# digital_supply.net
KiCad netlist of a schematic drawn in EAGLE
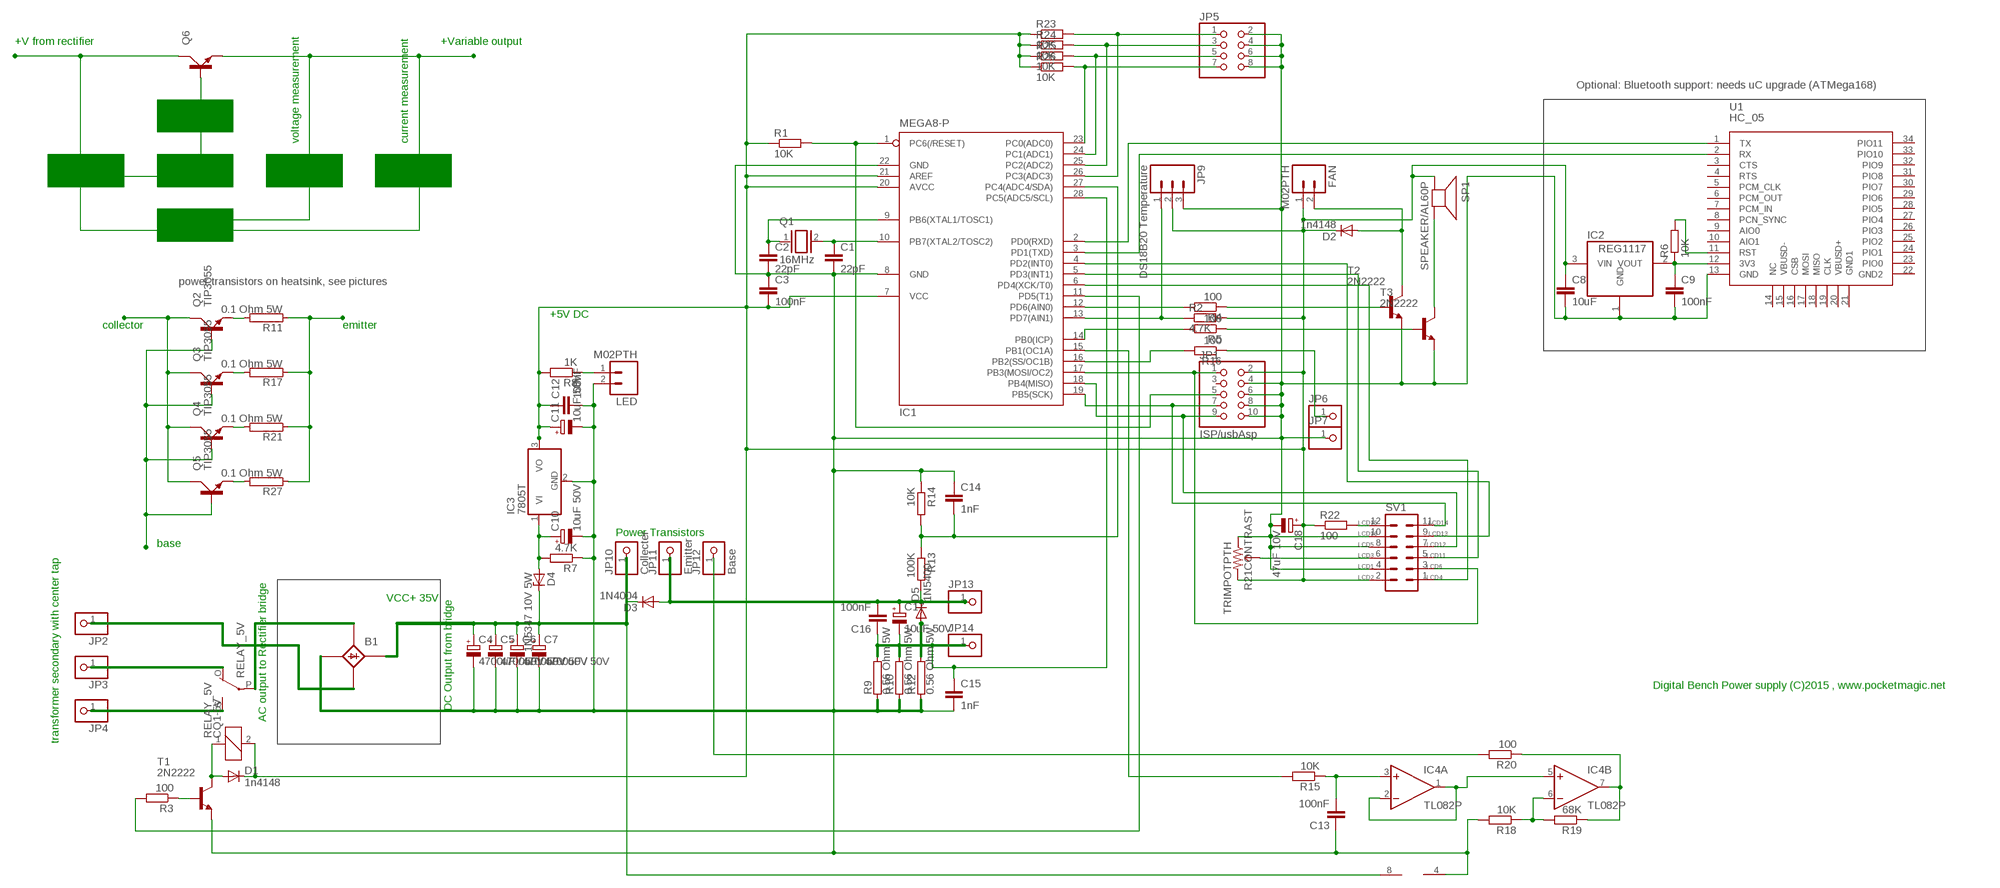
[diagram p0: schematic, sheet 1]

(export (version "E")
  (design (tool "Eeschema 10.0.6"))
  (components
    (comp (ref "B1")
      (value "B25A-")
      (footprint "eagle-import:B25A-")
      (libsource (lib "eagle-import") (part "B25A-"))
    )
    (comp (ref "C1")
      (value "22pF")
      (footprint "eagle-import:C025-024X044")
      (libsource (lib "eagle-import") (part "C-EU025-024X044"))
    )
    (comp (ref "C2")
      (value "22pF")
      (footprint "eagle-import:C025-024X044")
      (libsource (lib "eagle-import") (part "C-EU025-024X044"))
    )
    (comp (ref "C3")
      (value "100nF")
      (footprint "eagle-import:C025-024X044")
      (libsource (lib "eagle-import") (part "C-EU025-024X044"))
    )
    (comp (ref "C4")
      (value "4700uF / 50V")
      (footprint "eagle-import:E7,5-18")
      (libsource (lib "eagle-import") (part "CPOL-EUE7.5-18"))
    )
    (comp (ref "C5")
      (value "4700uF / 50V")
      (footprint "eagle-import:E7,5-18")
      (libsource (lib "eagle-import") (part "CPOL-EUE7.5-18"))
    )
    (comp (ref "C6")
      (value "4700uF / 50V")
      (footprint "eagle-import:E7,5-18")
      (libsource (lib "eagle-import") (part "CPOL-EUE7.5-18"))
    )
    (comp (ref "C7")
      (value "4700uF / 50V")
      (footprint "eagle-import:E7,5-18")
      (libsource (lib "eagle-import") (part "CPOL-EUE7.5-18"))
    )
    (comp (ref "C8")
      (value "10uF")
      (footprint "eagle-import:C0805")
      (libsource (lib "eagle-import") (part "resistor_C-EUC0805"))
    )
    (comp (ref "C9")
      (value "100nF")
      (footprint "eagle-import:C0805")
      (libsource (lib "eagle-import") (part "resistor_C-EUC0805"))
    )
    (comp (ref "C10")
      (value "10uF 50V")
      (footprint "eagle-import:E2-5")
      (libsource (lib "eagle-import") (part "CPOL-EUE2-5"))
    )
    (comp (ref "C11")
      (value "10uF 50V")
      (footprint "eagle-import:E2-5")
      (libsource (lib "eagle-import") (part "CPOL-EUE2-5"))
    )
    (comp (ref "C12")
      (value "100nF")
      (footprint "eagle-import:C025-024X044")
      (libsource (lib "eagle-import") (part "C-EU025-024X044"))
    )
    (comp (ref "C13")
      (value "100nF")
      (footprint "eagle-import:C025-024X044")
      (libsource (lib "eagle-import") (part "C-EU025-024X044"))
    )
    (comp (ref "C14")
      (value "1nF")
      (footprint "eagle-import:C025-024X044")
      (libsource (lib "eagle-import") (part "C-EU025-024X044"))
    )
    (comp (ref "C15")
      (value "1nF")
      (footprint "eagle-import:C025-024X044")
      (libsource (lib "eagle-import") (part "C-EU025-024X044"))
    )
    (comp (ref "C16")
      (value "100nF")
      (footprint "eagle-import:C025-024X044")
      (libsource (lib "eagle-import") (part "C-EU025-024X044"))
    )
    (comp (ref "C17")
      (value "10uF 50V")
      (footprint "eagle-import:E2-5")
      (libsource (lib "eagle-import") (part "CPOL-EUE2-5"))
    )
    (comp (ref "C18")
      (value "47uF 10V")
      (footprint "eagle-import:E2-5")
      (libsource (lib "eagle-import") (part "CPOL-EUE2-5"))
    )
    (comp (ref "D1")
      (value "1n4148")
      (footprint "eagle-import:D-5")
      (libsource (lib "eagle-import") (part "DIODE-D-5"))
    )
    (comp (ref "D2")
      (value "1n4148")
      (footprint "eagle-import:D-5")
      (libsource (lib "eagle-import") (part "DIODE-D-5"))
    )
    (comp (ref "D3")
      (value "1N4004")
      (footprint "eagle-import:DO41-10")
      (libsource (lib "eagle-import") (part "1N4004"))
    )
    (comp (ref "D4")
      (value "1N5347 10V 5W")
      (footprint "eagle-import:DO34Z7")
      (libsource (lib "eagle-import") (part "ZENER-DIODEDO34-7"))
    )
    (comp (ref "D5")
      (value "1N5400")
      (footprint "eagle-import:DO201-15")
      (libsource (lib "eagle-import") (part "1N5400"))
    )
    (comp (ref "FAN")
      (value "M02PTH")
      (footprint "eagle-import:1X02")
      (libsource (lib "eagle-import") (part "M02PTH"))
    )
    (comp (ref "IC1")
      (value "MEGA8-P")
      (footprint "eagle-import:DIL28-3")
      (libsource (lib "eagle-import") (part "MEGA8-P"))
    )
    (comp (ref "IC2")
      (value "REG1117")
      (footprint "eagle-import:SOT223")
      (libsource (lib "eagle-import") (part "REG1117"))
    )
    (comp (ref "IC3")
      (value "7805T")
      (footprint "eagle-import:TO220H")
      (libsource (lib "eagle-import") (part "78T05"))
    )
    (comp (ref "IC4")
      (value "TL082P")
      (footprint "eagle-import:DIL08")
      (libsource (lib "eagle-import") (part "TL082P"))
    )
    (comp (ref "JP1")
      (value "ISP/usbAsp")
      (footprint "eagle-import:2X05")
      (libsource (lib "eagle-import") (part "PINHD-2X5"))
    )
    (comp (ref "JP2")
      (value "PINHD-1X1")
      (footprint "eagle-import:1X01")
      (libsource (lib "eagle-import") (part "PINHD-1X1"))
    )
    (comp (ref "JP3")
      (value "PINHD-1X1")
      (footprint "eagle-import:1X01")
      (libsource (lib "eagle-import") (part "PINHD-1X1"))
    )
    (comp (ref "JP4")
      (value "PINHD-1X1")
      (footprint "eagle-import:1X01")
      (libsource (lib "eagle-import") (part "PINHD-1X1"))
    )
    (comp (ref "JP5")
      (value "PINHD-2X4")
      (footprint "eagle-import:2X04")
      (libsource (lib "eagle-import") (part "PINHD-2X4"))
    )
    (comp (ref "JP6")
      (value "PINHD-1X1")
      (footprint "eagle-import:1X01")
      (libsource (lib "eagle-import") (part "PINHD-1X1"))
    )
    (comp (ref "JP7")
      (value "PINHD-1X1")
      (footprint "eagle-import:1X01")
      (libsource (lib "eagle-import") (part "PINHD-1X1"))
    )
    (comp (ref "JP9")
      (value "DS18B20 Temperature")
      (footprint "eagle-import:1X03")
      (libsource (lib "eagle-import") (part "M03PTH"))
    )
    (comp (ref "JP10")
      (value "Collecter")
      (footprint "eagle-import:1X01")
      (libsource (lib "eagle-import") (part "PINHD-1X1"))
    )
    (comp (ref "JP11")
      (value "Emitter")
      (footprint "eagle-import:1X01")
      (libsource (lib "eagle-import") (part "PINHD-1X1"))
    )
    (comp (ref "JP12")
      (value "Base")
      (footprint "eagle-import:1X01")
      (libsource (lib "eagle-import") (part "PINHD-1X1"))
    )
    (comp (ref "JP13")
      (value "PINHD-1X1")
      (footprint "eagle-import:1X01")
      (libsource (lib "eagle-import") (part "PINHD-1X1"))
    )
    (comp (ref "JP14")
      (value "PINHD-1X1")
      (footprint "eagle-import:1X01")
      (libsource (lib "eagle-import") (part "PINHD-1X1"))
    )
    (comp (ref "LED")
      (value "M02PTH")
      (footprint "eagle-import:1X02")
      (libsource (lib "eagle-import") (part "M02PTH"))
    )
    (comp (ref "Q1")
      (value "16MHz")
      (footprint "eagle-import:QS")
      (libsource (lib "eagle-import") (part "XTAL/S"))
    )
    (comp (ref "Q2")
      (value "TIP3055")
      (footprint "eagle-import:TOP3AV")
      (libsource (lib "eagle-import") (part "TIP3055"))
    )
    (comp (ref "Q3")
      (value "TIP3055")
      (footprint "eagle-import:TOP3AV")
      (libsource (lib "eagle-import") (part "TIP3055"))
    )
    (comp (ref "Q4")
      (value "TIP3055")
      (footprint "eagle-import:TOP3AV")
      (libsource (lib "eagle-import") (part "TIP3055"))
    )
    (comp (ref "Q5")
      (value "TIP3055")
      (footprint "eagle-import:TOP3AV")
      (libsource (lib "eagle-import") (part "TIP3055"))
    )
    (comp (ref "Q6")
      (value "TIP3055")
      (footprint "eagle-import:TOP3AV")
      (libsource (lib "eagle-import") (part "TIP3055"))
    )
    (comp (ref "R1")
      (value "10K")
      (footprint "eagle-import:0204_7")
      (libsource (lib "eagle-import") (part "R-EU_0204/7"))
    )
    (comp (ref "R2")
      (value "4.7K")
      (footprint "eagle-import:0204_7")
      (libsource (lib "eagle-import") (part "R-EU_0204/7"))
    )
    (comp (ref "R3")
      (value "100")
      (footprint "eagle-import:0204_7")
      (libsource (lib "eagle-import") (part "R-EU_0204/7"))
    )
    (comp (ref "R4")
      (value "100")
      (footprint "eagle-import:0204_7")
      (libsource (lib "eagle-import") (part "R-EU_0204/7"))
    )
    (comp (ref "R5")
      (value "100")
      (footprint "eagle-import:0204_7")
      (libsource (lib "eagle-import") (part "R-EU_0204/7"))
    )
    (comp (ref "R6")
      (value "10K")
      (footprint "eagle-import:M0805")
      (libsource (lib "eagle-import") (part "R-EU_M0805"))
    )
    (comp (ref "R7")
      (value "4.7K")
      (footprint "eagle-import:0204_7")
      (libsource (lib "eagle-import") (part "R-EU_0204/7"))
    )
    (comp (ref "R8")
      (value "1K")
      (footprint "eagle-import:0204_7")
      (libsource (lib "eagle-import") (part "R-EU_0204/7"))
    )
    (comp (ref "R9")
      (value "0.56 Ohm 5W")
      (footprint "eagle-import:AC05")
      (libsource (lib "eagle-import") (part "RAC05"))
    )
    (comp (ref "R10")
      (value "0.56 Ohm 5W")
      (footprint "eagle-import:AC05")
      (libsource (lib "eagle-import") (part "RAC05"))
    )
    (comp (ref "R11")
      (value "0.1 Ohm 5W")
      (footprint "eagle-import:AC05")
      (fields (field (name "OC_FARNELL") "unknown") (field (name "OC_NEWARK") "unknown"))
      (libsource (lib "eagle-import") (part "RAC05"))
    )
    (comp (ref "R12")
      (value "0.56 Ohm 5W")
      (footprint "eagle-import:AC05")
      (fields (field (name "OC_FARNELL") "unknown") (field (name "OC_NEWARK") "unknown"))
      (libsource (lib "eagle-import") (part "RAC05"))
    )
    (comp (ref "R13")
      (value "100K")
      (footprint "eagle-import:0204_7")
      (libsource (lib "eagle-import") (part "R-EU_0204/7"))
    )
    (comp (ref "R14")
      (value "10K")
      (footprint "eagle-import:0204_7")
      (libsource (lib "eagle-import") (part "R-EU_0204/7"))
    )
    (comp (ref "R15")
      (value "10K")
      (footprint "eagle-import:0204_7")
      (libsource (lib "eagle-import") (part "R-EU_0204/7"))
    )
    (comp (ref "R16")
      (value "100")
      (footprint "eagle-import:0204_7")
      (libsource (lib "eagle-import") (part "R-EU_0204/7"))
    )
    (comp (ref "R17")
      (value "0.1 Ohm 5W")
      (footprint "eagle-import:AC05")
      (fields (field (name "OC_FARNELL") "unknown") (field (name "OC_NEWARK") "unknown"))
      (libsource (lib "eagle-import") (part "RAC05"))
    )
    (comp (ref "R18")
      (value "10K")
      (footprint "eagle-import:0204_7")
      (libsource (lib "eagle-import") (part "R-EU_0204/7"))
    )
    (comp (ref "R19")
      (value "68K")
      (footprint "eagle-import:0204_7")
      (libsource (lib "eagle-import") (part "R-EU_0204/7"))
    )
    (comp (ref "R20")
      (value "100")
      (footprint "eagle-import:0204_7")
      (libsource (lib "eagle-import") (part "R-EU_0204/7"))
    )
    (comp (ref "R21")
      (value "0.1 Ohm 5W")
      (footprint "eagle-import:AC05")
      (fields (field (name "OC_FARNELL") "unknown") (field (name "OC_NEWARK") "unknown"))
      (libsource (lib "eagle-import") (part "RAC05"))
    )
    (comp (ref "R21CONTRAST")
      (value "TRIMPOTPTH")
      (footprint "eagle-import:TRIM_POT_PTH")
      (libsource (lib "eagle-import") (part "TRIMPOTPTH"))
    )
    (comp (ref "R22")
      (value "100")
      (footprint "eagle-import:0204_7")
      (libsource (lib "eagle-import") (part "R-EU_0204/7"))
    )
    (comp (ref "R23")
      (value "10K")
      (footprint "eagle-import:0204_7")
      (libsource (lib "eagle-import") (part "R-EU_0204/7"))
    )
    (comp (ref "R24")
      (value "10K")
      (footprint "eagle-import:0204_7")
      (libsource (lib "eagle-import") (part "R-EU_0204/7"))
    )
    (comp (ref "R25")
      (value "10K")
      (footprint "eagle-import:0204_7")
      (libsource (lib "eagle-import") (part "R-EU_0204/7"))
    )
    (comp (ref "R26")
      (value "10K")
      (footprint "eagle-import:0204_7")
      (libsource (lib "eagle-import") (part "R-EU_0204/7"))
    )
    (comp (ref "R27")
      (value "0.1 Ohm 5W")
      (footprint "eagle-import:AC05")
      (fields (field (name "OC_FARNELL") "unknown") (field (name "OC_NEWARK") "unknown"))
      (libsource (lib "eagle-import") (part "RAC05"))
    )
    (comp (ref "RELAY_5V")
      (value "CQ1-5V")
      (footprint "eagle-import:G5LE")
      (libsource (lib "eagle-import") (part "G5LE"))
    )
    (comp (ref "SP1")
      (value "SPEAKER/AL60P")
      (footprint "eagle-import:AL60P")
      (libsource (lib "eagle-import") (part "SPEAKER/AL60P"))
    )
    (comp (ref "SV1")
      (value "MA06-2")
      (footprint "eagle-import:MA06-2")
      (libsource (lib "eagle-import") (part "MA06-2"))
    )
    (comp (ref "T1")
      (value "2N2222")
      (footprint "eagle-import:TO92-EBC-OVAL")
      (libsource (lib "eagle-import") (part "2N2222"))
    )
    (comp (ref "T2")
      (value "2N2222")
      (footprint "eagle-import:TO92-EBC-OVAL")
      (libsource (lib "eagle-import") (part "2N2222"))
    )
    (comp (ref "T3")
      (value "2N2222")
      (footprint "eagle-import:TO92-EBC-OVAL")
      (libsource (lib "eagle-import") (part "2N2222"))
    )
    (comp (ref "U1")
      (value "HC_05")
      (footprint "eagle-import:BLUETOOTH_SMD")
      (libsource (lib "eagle-import") (part "HC_05"))
    )
  )
  (nets
    (net (code "1") (name "Net-(B1-AC1-PadAC1-)") (class "Default")
      (node (ref "B1") (pin "AC1-") (pinfunction "AC1_AC1-") (pintype "passive"))
      (node (ref "RELAY_5V") (pin "P") (pinfunction "P_P") (pintype "passive"))
    )
    (net (code "2") (name "Net-(B1-AC2-PadAC2-)") (class "Default")
      (node (ref "B1") (pin "AC2-") (pinfunction "AC2_AC2-") (pintype "passive"))
      (node (ref "JP2") (pin "1") (pinfunction "1_1") (pintype "passive"))
    )
    (net (code "3") (name "Net-(C16-Pad2)") (class "Default")
      (node (ref "C16") (pin "2") (pinfunction "2_2") (pintype "passive"))
      (node (ref "C17") (pin "+") (pinfunction "+_+") (pintype "passive"))
      (node (ref "D3") (pin "A") (pinfunction "A_A") (pintype "passive"))
      (node (ref "D5") (pin "C") (pinfunction "C_C") (pintype "passive"))
      (node (ref "JP11") (pin "1") (pinfunction "1_1") (pintype "passive"))
      (node (ref "JP13") (pin "1") (pinfunction "1_1") (pintype "passive"))
      (node (ref "R13") (pin "2") (pinfunction "2_2") (pintype "passive"))
    )
    (net (code "4") (name "Net-(D1-PadA)") (class "Default")
      (node (ref "D1") (pin "A") (pinfunction "A_A") (pintype "passive"))
      (node (ref "RELAY_5V") (pin "1") (pinfunction "1_1") (pintype "passive"))
      (node (ref "T1") (pin "C") (pinfunction "C_C") (pintype "passive"))
    )
    (net (code "5") (name "Net-(D2-PadA)") (class "Default")
      (node (ref "D2") (pin "A") (pinfunction "A_A") (pintype "passive"))
      (node (ref "FAN") (pin "2") (pinfunction "2_2") (pintype "passive"))
      (node (ref "T2") (pin "C") (pinfunction "C_C") (pintype "passive"))
    )
    (net (code "6") (name "Net-(IC1-AREF)") (class "Default")
      (node (ref "C11") (pin "+") (pinfunction "+_+") (pintype "passive"))
      (node (ref "C12") (pin "1") (pinfunction "1_1") (pintype "passive"))
      (node (ref "C18") (pin "+") (pinfunction "+_+") (pintype "passive"))
      (node (ref "C3") (pin "2") (pinfunction "2_2") (pintype "passive"))
      (node (ref "C8") (pin "1") (pinfunction "1_1") (pintype "passive"))
      (node (ref "D1") (pin "C") (pinfunction "C_C") (pintype "passive"))
      (node (ref "D2") (pin "C") (pinfunction "C_C") (pintype "passive"))
      (node (ref "FAN") (pin "1") (pinfunction "1_1") (pintype "passive"))
      (node (ref "IC1") (pin "20") (pinfunction "AVCC_20") (pintype "power_in"))
      (node (ref "IC1") (pin "21") (pinfunction "AREF_21") (pintype "passive"))
      (node (ref "IC1") (pin "7") (pinfunction "VCC_7") (pintype "power_in"))
      (node (ref "IC2") (pin "3") (pinfunction "VIN_3") (pintype "input"))
      (node (ref "IC3") (pin "3") (pinfunction "VO_3") (pintype "passive"))
      (node (ref "JP1") (pin "2") (pinfunction "2_2") (pintype "passive"))
      (node (ref "JP9") (pin "2") (pinfunction "2_2") (pintype "passive"))
      (node (ref "R1") (pin "1") (pinfunction "1_1") (pintype "passive"))
      (node (ref "R2") (pin "2") (pinfunction "2_2") (pintype "passive"))
      (node (ref "R21CONTRAST") (pin "3") (pinfunction "CW_3") (pintype "passive"))
      (node (ref "R22") (pin "1") (pinfunction "1_1") (pintype "passive"))
      (node (ref "R23") (pin "1") (pinfunction "1_1") (pintype "passive"))
      (node (ref "R24") (pin "1") (pinfunction "1_1") (pintype "passive"))
      (node (ref "R25") (pin "1") (pinfunction "1_1") (pintype "passive"))
      (node (ref "R26") (pin "1") (pinfunction "1_1") (pintype "passive"))
      (node (ref "R8") (pin "2") (pinfunction "2_2") (pintype "passive"))
      (node (ref "RELAY_5V") (pin "2") (pinfunction "2_2") (pintype "passive"))
      (node (ref "SP1") (pin "1") (pinfunction "+_1") (pintype "passive"))
      (node (ref "SV1") (pin "2") (pinfunction "2_2") (pintype "passive"))
    )
    (net (code "7") (name "Net-(IC1-PB0(ICP))") (class "Default")
      (node (ref "IC1") (pin "14") (pinfunction "PB0(ICP)_14") (pintype "bidirectional"))
      (node (ref "R5") (pin "2") (pinfunction "2_2") (pintype "passive"))
    )
    (net (code "8") (name "Net-(IC1-PB1(OC1A))") (class "Default")
      (node (ref "IC1") (pin "15") (pinfunction "PB1(OC1A)_15") (pintype "bidirectional"))
      (node (ref "R15") (pin "2") (pinfunction "2_2") (pintype "passive"))
    )
    (net (code "9") (name "Net-(IC1-PB2(SS{slash}OC1B))") (class "Default")
      (node (ref "IC1") (pin "16") (pinfunction "PB2(SS/OC1B)_16") (pintype "bidirectional"))
      (node (ref "R16") (pin "2") (pinfunction "2_2") (pintype "passive"))
    )
    (net (code "10") (name "Net-(IC1-PB3(MOSI{slash}OC2))") (class "Default")
      (node (ref "IC1") (pin "17") (pinfunction "PB3(MOSI/OC2)_17") (pintype "bidirectional"))
      (node (ref "JP1") (pin "1") (pinfunction "1_1") (pintype "passive"))
      (node (ref "SV1") (pin "3") (pinfunction "3_3") (pintype "passive"))
    )
    (net (code "11") (name "Net-(IC1-PB4(MISO))") (class "Default")
      (node (ref "IC1") (pin "18") (pinfunction "PB4(MISO)_18") (pintype "bidirectional"))
      (node (ref "JP1") (pin "9") (pinfunction "9_9") (pintype "passive"))
      (node (ref "SV1") (pin "7") (pinfunction "7_7") (pintype "passive"))
    )
    (net (code "12") (name "Net-(IC1-PB5(SCK))") (class "Default")
      (node (ref "IC1") (pin "19") (pinfunction "PB5(SCK)_19") (pintype "bidirectional"))
      (node (ref "JP1") (pin "7") (pinfunction "7_7") (pintype "passive"))
      (node (ref "SV1") (pin "11") (pinfunction "11_11") (pintype "passive"))
    )
    (net (code "13") (name "Net-(IC1-PB6(XTAL1{slash}TOSC1))") (class "Default")
      (node (ref "C2") (pin "1") (pinfunction "1_1") (pintype "passive"))
      (node (ref "IC1") (pin "9") (pinfunction "PB6(XTAL1/TOSC1)_9") (pintype "bidirectional"))
      (node (ref "Q1") (pin "1") (pinfunction "1_1") (pintype "passive"))
    )
    (net (code "14") (name "Net-(IC1-PB7(XTAL2{slash}TOSC2))") (class "Default")
      (node (ref "C1") (pin "1") (pinfunction "1_1") (pintype "passive"))
      (node (ref "IC1") (pin "10") (pinfunction "PB7(XTAL2/TOSC2)_10") (pintype "bidirectional"))
      (node (ref "Q1") (pin "2") (pinfunction "2_2") (pintype "passive"))
    )
    (net (code "15") (name "Net-(IC1-PC0(ADC0))") (class "Default")
      (node (ref "IC1") (pin "23") (pinfunction "PC0(ADC0)_23") (pintype "bidirectional"))
      (node (ref "JP5") (pin "7") (pinfunction "7_7") (pintype "passive"))
      (node (ref "R26") (pin "2") (pinfunction "2_2") (pintype "passive"))
    )
    (net (code "16") (name "Net-(IC1-PC1(ADC1))") (class "Default")
      (node (ref "IC1") (pin "24") (pinfunction "PC1(ADC1)_24") (pintype "bidirectional"))
      (node (ref "JP5") (pin "5") (pinfunction "5_5") (pintype "passive"))
      (node (ref "R25") (pin "2") (pinfunction "2_2") (pintype "passive"))
    )
    (net (code "17") (name "Net-(IC1-PC2(ADC2))") (class "Default")
      (node (ref "IC1") (pin "25") (pinfunction "PC2(ADC2)_25") (pintype "bidirectional"))
      (node (ref "JP5") (pin "3") (pinfunction "3_3") (pintype "passive"))
      (node (ref "R24") (pin "2") (pinfunction "2_2") (pintype "passive"))
    )
    (net (code "18") (name "Net-(IC1-PC3(ADC3))") (class "Default")
      (node (ref "IC1") (pin "26") (pinfunction "PC3(ADC3)_26") (pintype "bidirectional"))
      (node (ref "JP5") (pin "1") (pinfunction "1_1") (pintype "passive"))
      (node (ref "R23") (pin "2") (pinfunction "2_2") (pintype "passive"))
    )
    (net (code "19") (name "Net-(IC1-PC4(ADC4{slash}SDA))") (class "Default")
      (node (ref "C14") (pin "2") (pinfunction "2_2") (pintype "passive"))
      (node (ref "IC1") (pin "27") (pinfunction "PC4(ADC4/SDA)_27") (pintype "bidirectional"))
      (node (ref "R13") (pin "1") (pinfunction "1_1") (pintype "passive"))
      (node (ref "R14") (pin "2") (pinfunction "2_2") (pintype "passive"))
    )
    (net (code "20") (name "Net-(IC1-PC5(ADC5{slash}SCL))") (class "Default")
      (node (ref "C15") (pin "1") (pinfunction "1_1") (pintype "passive"))
      (node (ref "C16") (pin "1") (pinfunction "1_1") (pintype "passive"))
      (node (ref "C17") (pin "-") (pinfunction "-_-") (pintype "passive"))
      (node (ref "D5") (pin "A") (pinfunction "A_A") (pintype "passive"))
      (node (ref "IC1") (pin "28") (pinfunction "PC5(ADC5/SCL)_28") (pintype "bidirectional"))
      (node (ref "JP14") (pin "1") (pinfunction "1_1") (pintype "passive"))
      (node (ref "R10") (pin "2") (pinfunction "2_2") (pintype "passive"))
      (node (ref "R12") (pin "2") (pinfunction "2_2") (pintype "passive"))
      (node (ref "R9") (pin "2") (pinfunction "2_2") (pintype "passive"))
    )
    (net (code "21") (name "Net-(IC1-PC6({slash}RESET))") (class "Default")
      (node (ref "IC1") (pin "1") (pinfunction "PC6(/RESET)_1") (pintype "bidirectional"))
      (node (ref "JP1") (pin "5") (pinfunction "5_5") (pintype "passive"))
      (node (ref "R1") (pin "2") (pinfunction "2_2") (pintype "passive"))
    )
    (net (code "22") (name "Net-(IC1-PD0(RXD))") (class "Default")
      (node (ref "IC1") (pin "2") (pinfunction "PD0(RXD)_2") (pintype "bidirectional"))
      (node (ref "U1") (pin "1") (pinfunction "TX_1") (pintype "bidirectional"))
    )
    (net (code "23") (name "Net-(IC1-PD1(TXD))") (class "Default")
      (node (ref "IC1") (pin "3") (pinfunction "PD1(TXD)_3") (pintype "bidirectional"))
      (node (ref "U1") (pin "2") (pinfunction "RX_2") (pintype "bidirectional"))
    )
    (net (code "24") (name "Net-(IC1-PD2(INT0))") (class "Default")
      (node (ref "IC1") (pin "4") (pinfunction "PD2(INT0)_4") (pintype "bidirectional"))
      (node (ref "SV1") (pin "9") (pinfunction "9_9") (pintype "passive"))
    )
    (net (code "25") (name "Net-(IC1-PD3(INT1))") (class "Default")
      (node (ref "IC1") (pin "5") (pinfunction "PD3(INT1)_5") (pintype "bidirectional"))
      (node (ref "SV1") (pin "5") (pinfunction "5_5") (pintype "passive"))
    )
    (net (code "26") (name "Net-(IC1-PD4(XCK{slash}T0))") (class "Default")
      (node (ref "IC1") (pin "6") (pinfunction "PD4(XCK/T0)_6") (pintype "bidirectional"))
      (node (ref "SV1") (pin "1") (pinfunction "1_1") (pintype "passive"))
    )
    (net (code "27") (name "Net-(IC1-PD5(T1))") (class "Default")
      (node (ref "IC1") (pin "11") (pinfunction "PD5(T1)_11") (pintype "bidirectional"))
      (node (ref "R3") (pin "2") (pinfunction "2_2") (pintype "passive"))
    )
    (net (code "28") (name "Net-(IC1-PD6(AIN0))") (class "Default")
      (node (ref "IC1") (pin "12") (pinfunction "PD6(AIN0)_12") (pintype "bidirectional"))
      (node (ref "R4") (pin "2") (pinfunction "2_2") (pintype "passive"))
    )
    (net (code "29") (name "Net-(IC1-PD7(AIN1))") (class "Default")
      (node (ref "IC1") (pin "13") (pinfunction "PD7(AIN1)_13") (pintype "bidirectional"))
      (node (ref "JP9") (pin "1") (pinfunction "1_1") (pintype "passive"))
      (node (ref "R2") (pin "1") (pinfunction "1_1") (pintype "passive"))
    )
    (net (code "30") (name "Net-(IC2-GND)") (class "Default")
      (node (ref "B1") (pin "-1") (pinfunction "-_-1") (pintype "passive"))
      (node (ref "C1") (pin "2") (pinfunction "2_2") (pintype "passive"))
      (node (ref "C10") (pin "-") (pinfunction "-_-") (pintype "passive"))
      (node (ref "C11") (pin "-") (pinfunction "-_-") (pintype "passive"))
      (node (ref "C12") (pin "2") (pinfunction "2_2") (pintype "passive"))
      (node (ref "C13") (pin "1") (pinfunction "1_1") (pintype "passive"))
      (node (ref "C14") (pin "1") (pinfunction "1_1") (pintype "passive"))
      (node (ref "C15") (pin "2") (pinfunction "2_2") (pintype "passive"))
      (node (ref "C18") (pin "-") (pinfunction "-_-") (pintype "passive"))
      (node (ref "C2") (pin "2") (pinfunction "2_2") (pintype "passive"))
      (node (ref "C3") (pin "1") (pinfunction "1_1") (pintype "passive"))
      (node (ref "C4") (pin "-") (pinfunction "-_-") (pintype "passive"))
      (node (ref "C5") (pin "-") (pinfunction "-_-") (pintype "passive"))
      (node (ref "C6") (pin "-") (pinfunction "-_-") (pintype "passive"))
      (node (ref "C7") (pin "-") (pinfunction "-_-") (pintype "passive"))
      (node (ref "C8") (pin "2") (pinfunction "2_2") (pintype "passive"))
      (node (ref "C9") (pin "2") (pinfunction "2_2") (pintype "passive"))
      (node (ref "IC1") (pin "22") (pinfunction "GND_22") (pintype "power_in"))
      (node (ref "IC1") (pin "8") (pinfunction "GND_8") (pintype "power_in"))
      (node (ref "IC2") (pin "1") (pinfunction "GND_1") (pintype "power_in"))
      (node (ref "IC3") (pin "2") (pinfunction "GND_2") (pintype "passive"))
      (node (ref "IC4") (pin "4") (pinfunction "V-_4") (pintype "power_in"))
      (node (ref "JP1") (pin "10") (pinfunction "10_10") (pintype "passive"))
      (node (ref "JP1") (pin "4") (pinfunction "4_4") (pintype "passive"))
      (node (ref "JP1") (pin "6") (pinfunction "6_6") (pintype "passive"))
      (node (ref "JP1") (pin "8") (pinfunction "8_8") (pintype "passive"))
      (node (ref "JP5") (pin "2") (pinfunction "2_2") (pintype "passive"))
      (node (ref "JP5") (pin "4") (pinfunction "4_4") (pintype "passive"))
      (node (ref "JP5") (pin "6") (pinfunction "6_6") (pintype "passive"))
      (node (ref "JP5") (pin "8") (pinfunction "8_8") (pintype "passive"))
      (node (ref "JP7") (pin "1") (pinfunction "1_1") (pintype "passive"))
      (node (ref "JP9") (pin "3") (pinfunction "3_3") (pintype "passive"))
      (node (ref "LED") (pin "2") (pinfunction "2_2") (pintype "passive"))
      (node (ref "R10") (pin "1") (pinfunction "1_1") (pintype "passive"))
      (node (ref "R12") (pin "1") (pinfunction "1_1") (pintype "passive"))
      (node (ref "R14") (pin "1") (pinfunction "1_1") (pintype "passive"))
      (node (ref "R18") (pin "2") (pinfunction "2_2") (pintype "passive"))
      (node (ref "R21CONTRAST") (pin "1") (pinfunction "CCW_1") (pintype "passive"))
      (node (ref "R7") (pin "1") (pinfunction "1_1") (pintype "passive"))
      (node (ref "R9") (pin "1") (pinfunction "1_1") (pintype "passive"))
      (node (ref "SV1") (pin "10") (pinfunction "10_10") (pintype "passive"))
      (node (ref "SV1") (pin "4") (pinfunction "4_4") (pintype "passive"))
      (node (ref "SV1") (pin "8") (pinfunction "8_8") (pintype "passive"))
      (node (ref "T1") (pin "E") (pinfunction "E_E") (pintype "passive"))
      (node (ref "T2") (pin "E") (pinfunction "E_E") (pintype "passive"))
      (node (ref "T3") (pin "E") (pinfunction "E_E") (pintype "passive"))
      (node (ref "U1") (pin "13") (pinfunction "GND_13") (pintype "bidirectional"))
    )
    (net (code "31") (name "Net-(IC2-VOUT)") (class "Default")
      (node (ref "C9") (pin "1") (pinfunction "1_1") (pintype "passive"))
      (node (ref "IC2") (pin "2") (pinfunction "VOUT_2") (pintype "output"))
      (node (ref "R6") (pin "1") (pinfunction "1_1") (pintype "passive"))
      (node (ref "U1") (pin "12") (pinfunction "3V3_12") (pintype "bidirectional"))
    )
    (net (code "32") (name "Net-(IC3-VI)") (class "Default")
      (node (ref "C10") (pin "+") (pinfunction "+_+") (pintype "passive"))
      (node (ref "D4") (pin "A") (pinfunction "A_A") (pintype "passive"))
      (node (ref "IC3") (pin "1") (pinfunction "VI_1") (pintype "input"))
      (node (ref "R7") (pin "2") (pinfunction "2_2") (pintype "passive"))
    )
    (net (code "33") (name "Net-(IC4A-+IN)") (class "Default")
      (node (ref "C13") (pin "2") (pinfunction "2_2") (pintype "passive"))
      (node (ref "IC4") (pin "3") (pinfunction "+IN_3") (pintype "input"))
      (node (ref "R15") (pin "1") (pinfunction "1_1") (pintype "passive"))
    )
    (net (code "34") (name "Net-(IC4A--IN)") (class "Default")
      (node (ref "IC4") (pin "1") (pinfunction "OUT_1") (pintype "output"))
      (node (ref "IC4") (pin "2") (pinfunction "-IN_2") (pintype "input"))
      (node (ref "IC4") (pin "5") (pinfunction "+IN_5") (pintype "input"))
    )
    (net (code "35") (name "Net-(IC4B--IN)") (class "Default")
      (node (ref "IC4") (pin "6") (pinfunction "-IN_6") (pintype "input"))
      (node (ref "R18") (pin "1") (pinfunction "1_1") (pintype "passive"))
      (node (ref "R19") (pin "2") (pinfunction "2_2") (pintype "passive"))
    )
    (net (code "36") (name "Net-(IC4B-OUT)") (class "Default")
      (node (ref "IC4") (pin "7") (pinfunction "OUT_7") (pintype "output"))
      (node (ref "R19") (pin "1") (pinfunction "1_1") (pintype "passive"))
      (node (ref "R20") (pin "1") (pinfunction "1_1") (pintype "passive"))
    )
    (net (code "37") (name "Net-(IC4C-V+)") (class "Default")
      (node (ref "B1") (pin "+1") (pinfunction "+_+1") (pintype "passive"))
      (node (ref "C4") (pin "+") (pinfunction "+_+") (pintype "passive"))
      (node (ref "C5") (pin "+") (pinfunction "+_+") (pintype "passive"))
      (node (ref "C6") (pin "+") (pinfunction "+_+") (pintype "passive"))
      (node (ref "C7") (pin "+") (pinfunction "+_+") (pintype "passive"))
      (node (ref "D3") (pin "C") (pinfunction "C_C") (pintype "passive"))
      (node (ref "D4") (pin "C") (pinfunction "C_C") (pintype "passive"))
      (node (ref "IC4") (pin "8") (pinfunction "V+_8") (pintype "power_in"))
      (node (ref "JP10") (pin "1") (pinfunction "1_1") (pintype "passive"))
    )
    (net (code "38") (name "Net-(JP3-Pad1)") (class "Default")
      (node (ref "JP3") (pin "1") (pinfunction "1_1") (pintype "passive"))
      (node (ref "RELAY_5V") (pin "O") (pinfunction "O_O") (pintype "passive"))
    )
    (net (code "39") (name "Net-(JP4-Pad1)") (class "Default")
      (node (ref "JP4") (pin "1") (pinfunction "1_1") (pintype "passive"))
      (node (ref "RELAY_5V") (pin "S") (pinfunction "S_S") (pintype "passive"))
    )
    (net (code "40") (name "Net-(JP6-Pad1)") (class "Default")
      (node (ref "JP6") (pin "1") (pinfunction "1_1") (pintype "passive"))
      (node (ref "R16") (pin "1") (pinfunction "1_1") (pintype "passive"))
    )
    (net (code "41") (name "Net-(JP12-Pad1)") (class "Default")
      (node (ref "JP12") (pin "1") (pinfunction "1_1") (pintype "passive"))
      (node (ref "R20") (pin "2") (pinfunction "2_2") (pintype "passive"))
    )
    (net (code "42") (name "Net-(LED-Pad1)") (class "Default")
      (node (ref "LED") (pin "1") (pinfunction "1_1") (pintype "passive"))
      (node (ref "R8") (pin "1") (pinfunction "1_1") (pintype "passive"))
    )
    (net (code "43") (name "Net-(Q2-PadB)") (class "Default")
      (node (ref "Q2") (pin "B") (pinfunction "B_B") (pintype "passive"))
      (node (ref "Q3") (pin "B") (pinfunction "B_B") (pintype "passive"))
      (node (ref "Q4") (pin "B") (pinfunction "B_B") (pintype "passive"))
      (node (ref "Q5") (pin "B") (pinfunction "B_B") (pintype "passive"))
    )
    (net (code "44") (name "Net-(Q2-PadC)") (class "Default")
      (node (ref "Q2") (pin "C") (pinfunction "C_C") (pintype "passive"))
      (node (ref "Q3") (pin "C") (pinfunction "C_C") (pintype "passive"))
      (node (ref "Q4") (pin "C") (pinfunction "C_C") (pintype "passive"))
      (node (ref "Q5") (pin "C") (pinfunction "C_C") (pintype "passive"))
    )
    (net (code "45") (name "Net-(Q2-PadE)") (class "Default")
      (node (ref "Q2") (pin "E") (pinfunction "E_E") (pintype "passive"))
      (node (ref "R11") (pin "2") (pinfunction "2_2") (pintype "passive"))
    )
    (net (code "46") (name "Net-(Q3-PadE)") (class "Default")
      (node (ref "Q3") (pin "E") (pinfunction "E_E") (pintype "passive"))
      (node (ref "R17") (pin "2") (pinfunction "2_2") (pintype "passive"))
    )
    (net (code "47") (name "Net-(Q4-PadE)") (class "Default")
      (node (ref "Q4") (pin "E") (pinfunction "E_E") (pintype "passive"))
      (node (ref "R21") (pin "2") (pinfunction "2_2") (pintype "passive"))
    )
    (net (code "48") (name "Net-(Q5-PadE)") (class "Default")
      (node (ref "Q5") (pin "E") (pinfunction "E_E") (pintype "passive"))
      (node (ref "R27") (pin "2") (pinfunction "2_2") (pintype "passive"))
    )
    (net (code "49") (name "Net-(R3-Pad1)") (class "Default")
      (node (ref "R3") (pin "1") (pinfunction "1_1") (pintype "passive"))
      (node (ref "T1") (pin "B") (pinfunction "B_B") (pintype "passive"))
    )
    (net (code "50") (name "Net-(R4-Pad1)") (class "Default")
      (node (ref "R4") (pin "1") (pinfunction "1_1") (pintype "passive"))
      (node (ref "T2") (pin "B") (pinfunction "B_B") (pintype "passive"))
    )
    (net (code "51") (name "Net-(R5-Pad1)") (class "Default")
      (node (ref "R5") (pin "1") (pinfunction "1_1") (pintype "passive"))
      (node (ref "T3") (pin "B") (pinfunction "B_B") (pintype "passive"))
    )
    (net (code "52") (name "Net-(R11-Pad1)") (class "Default")
      (node (ref "R11") (pin "1") (pinfunction "1_1") (pintype "passive"))
      (node (ref "R17") (pin "1") (pinfunction "1_1") (pintype "passive"))
      (node (ref "R21") (pin "1") (pinfunction "1_1") (pintype "passive"))
      (node (ref "R27") (pin "1") (pinfunction "1_1") (pintype "passive"))
    )
    (net (code "53") (name "Net-(R21CONTRAST-WIPER)") (class "Default")
      (node (ref "R21CONTRAST") (pin "2") (pinfunction "WIPER_2") (pintype "passive"))
      (node (ref "SV1") (pin "6") (pinfunction "6_6") (pintype "passive"))
    )
    (net (code "54") (name "Net-(R22-Pad2)") (class "Default")
      (node (ref "R22") (pin "2") (pinfunction "2_2") (pintype "passive"))
      (node (ref "SV1") (pin "12") (pinfunction "12_12") (pintype "passive"))
    )
    (net (code "55") (name "Net-(SP1--)") (class "Default")
      (node (ref "SP1") (pin "2") (pinfunction "-_2") (pintype "passive"))
      (node (ref "T3") (pin "C") (pinfunction "C_C") (pintype "passive"))
    )
    (net (code "56") (name "Net-(U1-RST)") (class "Default")
      (node (ref "R6") (pin "2") (pinfunction "2_2") (pintype "passive"))
      (node (ref "U1") (pin "11") (pinfunction "RST_11") (pintype "bidirectional"))
    )
    (net (code "57") (name "unconnected-(B1-Pad+)") (class "Default")
      (node (ref "B1") (pin "+") (pinfunction "+_+") (pintype "passive"))
    )
    (net (code "58") (name "unconnected-(B1-Pad-)") (class "Default")
      (node (ref "B1") (pin "-") (pinfunction "-_-") (pintype "passive"))
    )
    (net (code "59") (name "unconnected-(B1-PadAC1)") (class "Default")
      (node (ref "B1") (pin "AC1") (pinfunction "AC1_AC1") (pintype "passive"))
    )
    (net (code "60") (name "unconnected-(B1-PadAC2)") (class "Default")
      (node (ref "B1") (pin "AC2") (pinfunction "AC2_AC2") (pintype "passive"))
    )
    (net (code "61") (name "unconnected-(JP1-Pad3)") (class "Default")
      (node (ref "JP1") (pin "3") (pinfunction "3_3") (pintype "passive"))
    )
    (net (code "62") (name "unconnected-(Q6-PadB)") (class "Default")
      (node (ref "Q6") (pin "B") (pinfunction "B_B") (pintype "passive"))
    )
    (net (code "63") (name "unconnected-(Q6-PadC)") (class "Default")
      (node (ref "Q6") (pin "C") (pinfunction "C_C") (pintype "passive"))
    )
    (net (code "64") (name "unconnected-(Q6-PadE)") (class "Default")
      (node (ref "Q6") (pin "E") (pinfunction "E_E") (pintype "passive"))
    )
    (net (code "65") (name "unconnected-(U1-AIO0-Pad9)") (class "Default")
      (node (ref "U1") (pin "9") (pinfunction "AIO0_9") (pintype "bidirectional"))
    )
    (net (code "66") (name "unconnected-(U1-AIO1-Pad10)") (class "Default")
      (node (ref "U1") (pin "10") (pinfunction "AIO1_10") (pintype "bidirectional"))
    )
    (net (code "67") (name "unconnected-(U1-CLK-Pad19)") (class "Default")
      (node (ref "U1") (pin "19") (pinfunction "CLK_19") (pintype "bidirectional"))
    )
    (net (code "68") (name "unconnected-(U1-CSB-Pad16)") (class "Default")
      (node (ref "U1") (pin "16") (pinfunction "CSB_16") (pintype "bidirectional"))
    )
    (net (code "69") (name "unconnected-(U1-CTS-Pad3)") (class "Default")
      (node (ref "U1") (pin "3") (pinfunction "CTS_3") (pintype "bidirectional"))
    )
    (net (code "70") (name "unconnected-(U1-GND1-Pad21)") (class "Default")
      (node (ref "U1") (pin "21") (pinfunction "GND1_21") (pintype "bidirectional"))
    )
    (net (code "71") (name "unconnected-(U1-GND2-Pad22)") (class "Default")
      (node (ref "U1") (pin "22") (pinfunction "GND2_22") (pintype "bidirectional"))
    )
    (net (code "72") (name "unconnected-(U1-MISO-Pad18)") (class "Default")
      (node (ref "U1") (pin "18") (pinfunction "MISO_18") (pintype "bidirectional"))
    )
    (net (code "73") (name "unconnected-(U1-MOSI-Pad17)") (class "Default")
      (node (ref "U1") (pin "17") (pinfunction "MOSI_17") (pintype "bidirectional"))
    )
    (net (code "74") (name "unconnected-(U1-NC-Pad14)") (class "Default")
      (node (ref "U1") (pin "14") (pinfunction "NC_14") (pintype "bidirectional"))
    )
    (net (code "75") (name "unconnected-(U1-PCM_CLK-Pad5)") (class "Default")
      (node (ref "U1") (pin "5") (pinfunction "PCM_CLK_5") (pintype "bidirectional"))
    )
    (net (code "76") (name "unconnected-(U1-PCM_IN-Pad7)") (class "Default")
      (node (ref "U1") (pin "7") (pinfunction "PCM_IN_7") (pintype "bidirectional"))
    )
    (net (code "77") (name "unconnected-(U1-PCM_OUT-Pad6)") (class "Default")
      (node (ref "U1") (pin "6") (pinfunction "PCM_OUT_6") (pintype "bidirectional"))
    )
    (net (code "78") (name "unconnected-(U1-PCN_SYNC-Pad8)") (class "Default")
      (node (ref "U1") (pin "8") (pinfunction "PCN_SYNC_8") (pintype "bidirectional"))
    )
    (net (code "79") (name "unconnected-(U1-PIO0-Pad23)") (class "Default")
      (node (ref "U1") (pin "23") (pinfunction "PIO0_23") (pintype "bidirectional"))
    )
    (net (code "80") (name "unconnected-(U1-PIO1-Pad24)") (class "Default")
      (node (ref "U1") (pin "24") (pinfunction "PIO1_24") (pintype "bidirectional"))
    )
    (net (code "81") (name "unconnected-(U1-PIO2-Pad25)") (class "Default")
      (node (ref "U1") (pin "25") (pinfunction "PIO2_25") (pintype "bidirectional"))
    )
    (net (code "82") (name "unconnected-(U1-PIO3-Pad26)") (class "Default")
      (node (ref "U1") (pin "26") (pinfunction "PIO3_26") (pintype "bidirectional"))
    )
    (net (code "83") (name "unconnected-(U1-PIO4-Pad27)") (class "Default")
      (node (ref "U1") (pin "27") (pinfunction "PIO4_27") (pintype "bidirectional"))
    )
    (net (code "84") (name "unconnected-(U1-PIO5-Pad28)") (class "Default")
      (node (ref "U1") (pin "28") (pinfunction "PIO5_28") (pintype "bidirectional"))
    )
    (net (code "85") (name "unconnected-(U1-PIO6-Pad29)") (class "Default")
      (node (ref "U1") (pin "29") (pinfunction "PIO6_29") (pintype "bidirectional"))
    )
    (net (code "86") (name "unconnected-(U1-PIO7-Pad30)") (class "Default")
      (node (ref "U1") (pin "30") (pinfunction "PIO7_30") (pintype "bidirectional"))
    )
    (net (code "87") (name "unconnected-(U1-PIO8-Pad31)") (class "Default")
      (node (ref "U1") (pin "31") (pinfunction "PIO8_31") (pintype "bidirectional"))
    )
    (net (code "88") (name "unconnected-(U1-PIO9-Pad32)") (class "Default")
      (node (ref "U1") (pin "32") (pinfunction "PIO9_32") (pintype "bidirectional"))
    )
    (net (code "89") (name "unconnected-(U1-PIO10-Pad33)") (class "Default")
      (node (ref "U1") (pin "33") (pinfunction "PIO10_33") (pintype "bidirectional"))
    )
    (net (code "90") (name "unconnected-(U1-PIO11-Pad34)") (class "Default")
      (node (ref "U1") (pin "34") (pinfunction "PIO11_34") (pintype "bidirectional"))
    )
    (net (code "91") (name "unconnected-(U1-RTS-Pad4)") (class "Default")
      (node (ref "U1") (pin "4") (pinfunction "RTS_4") (pintype "bidirectional"))
    )
    (net (code "92") (name "unconnected-(U1-VBUSD+-Pad20)") (class "Default")
      (node (ref "U1") (pin "20") (pinfunction "VBUSD+_20") (pintype "bidirectional"))
    )
    (net (code "93") (name "unconnected-(U1-VBUSD--Pad15)") (class "Default")
      (node (ref "U1") (pin "15") (pinfunction "VBUSD-_15") (pintype "bidirectional"))
    )
  )
)
